# Final_Schematic.net
KiCad netlist of a schematic drawn in Altium Designer
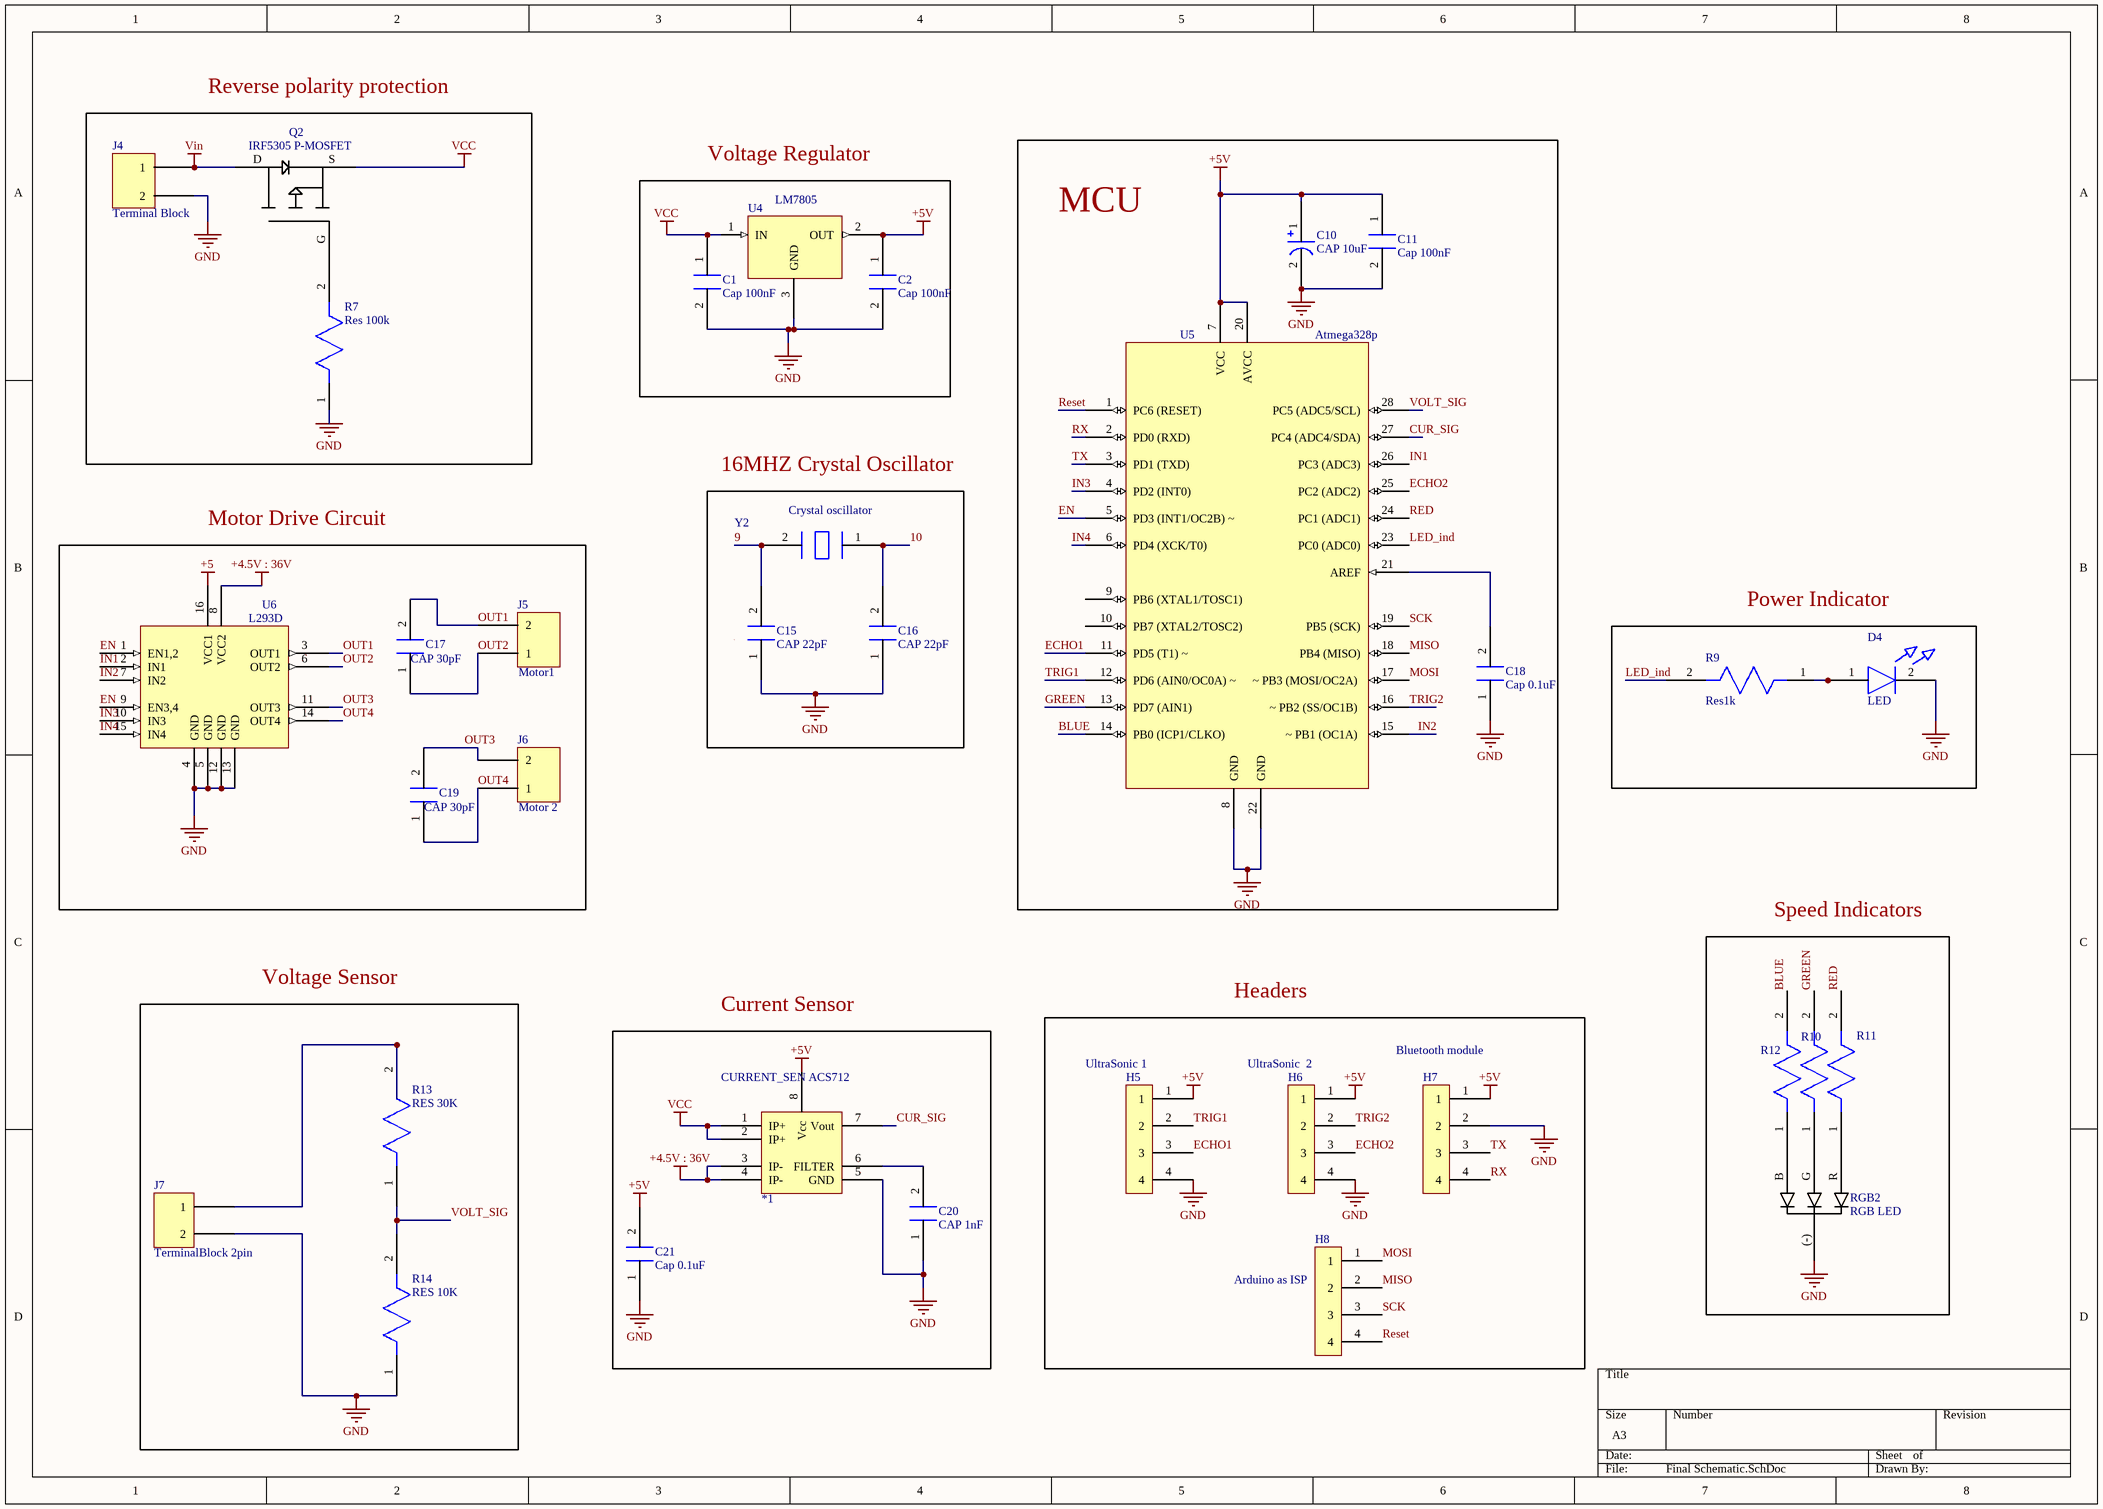
[diagram p0: Final Schematic.SchDoc]

(export (version "E")
  (design (tool "Eeschema 10.0.6"))
  (components
    (comp (ref "*1")
      (value "CURRENT_SEN ACS712")
      (footprint "Cuurent_sens")
      (libsource (lib "Schlib1") (part "CURRENT_MOD ACS712"))
    )
    (comp (ref "C1") (value "Cap 100nF") (libsource (lib "Schematic Library") (part "Cap 100nF")))
    (comp (ref "C2") (value "Cap 100nF") (libsource (lib "Schematic Library") (part "Cap 100nF")))
    (comp (ref "C10")
      (value "CAP 10uF")
      (footprint "Cap 10uF")
      (libsource (lib "Schematic Library") (part "CAP 10uF"))
    )
    (comp (ref "C11") (value "Cap 100nF") (libsource (lib "Schematic Library") (part "Cap 100nF")))
    (comp (ref "C15")
      (value "CAP 22pF")
      (footprint "Cap 22pF")
      (libsource (lib "Schematic Library") (part "CAP 22pF"))
    )
    (comp (ref "C16")
      (value "CAP 22pF")
      (footprint "Cap 22pF")
      (libsource (lib "Schematic Library") (part "CAP 22pF"))
    )
    (comp (ref "C17") (value "CAP 30pF") (libsource (lib "Schlib1") (part "CAP 30pF")))
    (comp (ref "C18") (value "Cap 0.1uF") (libsource (lib "Schematic Library") (part "Cap 0.1uF")))
    (comp (ref "C19") (value "CAP 30pF") (libsource (lib "Schlib1") (part "CAP 30pF")))
    (comp (ref "C20") (value "CAP 1nF") (footprint "CAP 1nF") (libsource (lib "Schlib1") (part "CAP 1nF")))
    (comp (ref "C21")
      (value "Cap 0.1uF")
      (footprint "CAP 0.1uF")
      (libsource (lib "Schlib1") (part "Cap 0.1uF"))
    )
    (comp (ref "D4") (value "LED") (footprint "LED") (libsource (lib "Schematic Library") (part "LED")))
    (comp (ref "H5")
      (value "UltraSonic 1")
      (footprint "Header 4pin")
      (libsource (lib "Schematic Library") (part "Headers 4pin_1"))
    )
    (comp (ref "H6")
      (value "UltraSonic  2")
      (footprint "Header 4pin")
      (libsource (lib "Schematic Library") (part "Headers 4pin_1"))
    )
    (comp (ref "H7")
      (value "Bluetooth module")
      (footprint "Header 4pin")
      (libsource (lib "Schematic Library") (part "Headers 4pin_1"))
    )
    (comp (ref "H8")
      (value "Arduino as ISP")
      (footprint "Header 4pin")
      (libsource (lib "Schematic Library") (part "Headers 4pin_1"))
    )
    (comp (ref "J4")
      (value "Terminal Block")
      (footprint "Terminal Block 2pin")
      (libsource (lib "") (part "Terminal Block_1"))
    )
    (comp (ref "J5")
      (value "Motor1")
      (footprint "Terminal Block 2pin")
      (libsource (lib "Schematic Library") (part "Terminal Block"))
    )
    (comp (ref "J6")
      (value "Motor 2")
      (footprint "Terminal Block 2pin")
      (libsource (lib "Schematic Library") (part "Terminal Block"))
    )
    (comp (ref "J7")
      (value "TerminalBlock 2pin")
      (footprint "Terminal Block 2pin")
      (libsource (lib "Schlib1") (part "TerminalBlock 2pin"))
    )
    (comp (ref "Q2")
      (value "IRF5305 P-MOSFET")
      (footprint "IRF5305")
      (libsource (lib "Schematic Library") (part "IRF5305 P-MOSFET"))
    )
    (comp (ref "R7")
      (value "Res 100k")
      (footprint "Res100K")
      (libsource (lib "Schematic Library") (part "Res 100k"))
    )
    (comp (ref "R9")
      (value "Res1k")
      (footprint "Res 1K")
      (libsource (lib "Schematic Library") (part "Res1k"))
    )
    (comp (ref "R10") (value "Resistor") (libsource (lib "Schematic Library") (part "Resistor")))
    (comp (ref "R11") (value "Resistor") (libsource (lib "Schematic Library") (part "Resistor")))
    (comp (ref "R12") (value "Resistor") (libsource (lib "Schematic Library") (part "Resistor")))
    (comp (ref "R13") (value "RES 30K") (footprint "Res100K") (libsource (lib "Schlib1") (part "RES 100K")))
    (comp (ref "R14") (value "RES 10K") (footprint "Res10K") (libsource (lib "Schlib1") (part "RES 10K")))
    (comp (ref "RGB2")
      (value "RGB LED")
      (footprint "RGB LED")
      (libsource (lib "Schematic Library") (part "RGB LED"))
    )
    (comp (ref "U4")
      (value "LM7805")
      (footprint "LM7805")
      (libsource (lib "Schematic Library") (part "LM7805"))
    )
    (comp (ref "U5")
      (value "Atmega328p")
      (footprint "ATMega 328 P-PU - duplicate")
      (libsource (lib "Schematic Library") (part "Atmega328p"))
    )
    (comp (ref "U6") (value "L293D") (footprint "L293D") (libsource (lib "Schematic Library") (part "L293D")))
    (comp (ref "Y2")
      (value "Crystal oscillator")
      (footprint "Crrystal 16MHZ")
      (libsource (lib "Schematic Library") (part "Crystal oscillator"))
    )
  )
  (nets
    (net (code "1") (name "+4.5V : 36V") (class "Default")
      (node (ref "*1") (pin "3") (pinfunction "IP-_3") (pintype "passive"))
      (node (ref "*1") (pin "4") (pinfunction "IP-_4") (pintype "passive"))
      (node (ref "U6") (pin "8") (pinfunction "VCC2_8") (pintype "power_in"))
    )
    (net (code "2") (name "+5") (class "Default")
      (node (ref "U6") (pin "16") (pinfunction "VCC1_16") (pintype "power_in"))
    )
    (net (code "3") (name "+5V") (class "Default")
      (node (ref "*1") (pin "8") (pinfunction "Vcc_8") (pintype "passive"))
      (node (ref "C10") (pin "1") (pinfunction "1_1") (pintype "passive"))
      (node (ref "C11") (pin "1") (pinfunction "1_1") (pintype "passive"))
      (node (ref "C2") (pin "1") (pinfunction "1_1") (pintype "passive"))
      (node (ref "C21") (pin "2") (pinfunction "2_2") (pintype "passive"))
      (node (ref "H5") (pin "1") (pinfunction "1_1") (pintype "passive"))
      (node (ref "H6") (pin "1") (pinfunction "1_1") (pintype "passive"))
      (node (ref "H7") (pin "1") (pinfunction "1_1") (pintype "passive"))
      (node (ref "U4") (pin "2") (pinfunction "OUT_2") (pintype "output"))
      (node (ref "U5") (pin "20") (pinfunction "AVCC_20") (pintype "passive"))
      (node (ref "U5") (pin "7") (pinfunction "VCC_7") (pintype "passive"))
    )
    (net (code "4") (name "/9") (class "Default")
      (node (ref "C15") (pin "2") (pinfunction "2_2") (pintype "passive"))
      (node (ref "Y2") (pin "2") (pinfunction "2_2") (pintype "passive"))
    )
    (net (code "5") (name "/10") (class "Default")
      (node (ref "C16") (pin "2") (pinfunction "2_2") (pintype "passive"))
      (node (ref "Y2") (pin "1") (pinfunction "1_1") (pintype "passive"))
    )
    (net (code "7") (name "/BLUE") (class "Default")
      (node (ref "R12") (pin "2") (pinfunction "4_2") (pintype "passive"))
      (node (ref "U5") (pin "14") (pinfunction "PB0_(ICP1/CLKO)_14") (pintype "bidirectional"))
    )
    (net (code "8") (name "/CUR_SIG") (class "Default")
      (node (ref "*1") (pin "7") (pinfunction "Vout_7") (pintype "passive"))
      (node (ref "U5") (pin "27") (pinfunction "PC4_(ADC4/SDA)_27") (pintype "bidirectional"))
    )
    (net (code "9") (name "/ECHO1") (class "Default")
      (node (ref "H5") (pin "3") (pinfunction "3_3") (pintype "passive"))
      (node (ref "U5") (pin "11") (pinfunction "PD5_(T1)_~_11") (pintype "bidirectional"))
    )
    (net (code "10") (name "/ECHO2") (class "Default")
      (node (ref "H6") (pin "3") (pinfunction "3_3") (pintype "passive"))
      (node (ref "U5") (pin "25") (pinfunction "PC2_(ADC2)_25") (pintype "bidirectional"))
    )
    (net (code "11") (name "/EN") (class "Default")
      (node (ref "U5") (pin "5") (pinfunction "PD3_(INT1/OC2B)_~_5") (pintype "bidirectional"))
      (node (ref "U6") (pin "1") (pinfunction "EN1,2_1") (pintype "input"))
      (node (ref "U6") (pin "9") (pinfunction "EN3,4_9") (pintype "input"))
    )
    (net (code "12") (name "/GREEN") (class "Default")
      (node (ref "R10") (pin "2") (pinfunction "4_2") (pintype "passive"))
      (node (ref "U5") (pin "13") (pinfunction "PD7_(AIN1)_13") (pintype "bidirectional"))
    )
    (net (code "13") (name "/IN1") (class "Default")
      (node (ref "U5") (pin "26") (pinfunction "PC3_(ADC3)_26") (pintype "bidirectional"))
      (node (ref "U6") (pin "2") (pinfunction "IN1_2") (pintype "input"))
    )
    (net (code "14") (name "/IN2") (class "Default")
      (node (ref "U5") (pin "15") (pinfunction "~_PB1_(OC1A)_15") (pintype "bidirectional"))
      (node (ref "U6") (pin "7") (pinfunction "IN2_7") (pintype "input"))
    )
    (net (code "15") (name "/IN3") (class "Default")
      (node (ref "U5") (pin "4") (pinfunction "PD2_(INT0)_4") (pintype "bidirectional"))
      (node (ref "U6") (pin "10") (pinfunction "IN3_10") (pintype "input"))
    )
    (net (code "16") (name "/IN4") (class "Default")
      (node (ref "U5") (pin "6") (pinfunction "PD4_(XCK/T0)_6") (pintype "bidirectional"))
      (node (ref "U6") (pin "15") (pinfunction "IN4_15") (pintype "input"))
    )
    (net (code "17") (name "/LED_ind") (class "Default")
      (node (ref "R9") (pin "2") (pinfunction "4_2") (pintype "passive"))
      (node (ref "U5") (pin "23") (pinfunction "PC0_(ADC0)_23") (pintype "bidirectional"))
    )
    (net (code "18") (name "/MISO") (class "Default")
      (node (ref "H8") (pin "2") (pinfunction "2_2") (pintype "passive"))
      (node (ref "U5") (pin "18") (pinfunction "PB4_(MISO)_18") (pintype "bidirectional"))
    )
    (net (code "19") (name "/MOSI") (class "Default")
      (node (ref "H8") (pin "1") (pinfunction "1_1") (pintype "passive"))
      (node (ref "U5") (pin "17") (pinfunction "~_PB3_(MOSI/OC2A)_17") (pintype "bidirectional"))
    )
    (net (code "20") (name "/OUT1") (class "Default")
      (node (ref "C17") (pin "2") (pinfunction "2_2") (pintype "passive"))
      (node (ref "J5") (pin "2") (pinfunction "2_2") (pintype "passive"))
      (node (ref "U6") (pin "3") (pinfunction "OUT1_3") (pintype "output"))
    )
    (net (code "21") (name "/OUT2") (class "Default")
      (node (ref "C17") (pin "1") (pinfunction "1_1") (pintype "passive"))
      (node (ref "J5") (pin "1") (pinfunction "1_1") (pintype "passive"))
      (node (ref "U6") (pin "6") (pinfunction "OUT2_6") (pintype "output"))
    )
    (net (code "22") (name "/OUT3") (class "Default")
      (node (ref "C19") (pin "2") (pinfunction "2_2") (pintype "passive"))
      (node (ref "J6") (pin "2") (pinfunction "2_2") (pintype "passive"))
      (node (ref "U6") (pin "11") (pinfunction "OUT3_11") (pintype "output"))
    )
    (net (code "23") (name "/OUT4") (class "Default")
      (node (ref "C19") (pin "1") (pinfunction "1_1") (pintype "passive"))
      (node (ref "J6") (pin "1") (pinfunction "1_1") (pintype "passive"))
      (node (ref "U6") (pin "14") (pinfunction "OUT4_14") (pintype "output"))
    )
    (net (code "24") (name "/RED") (class "Default")
      (node (ref "R11") (pin "2") (pinfunction "4_2") (pintype "passive"))
      (node (ref "U5") (pin "24") (pinfunction "PC1_(ADC1)_24") (pintype "bidirectional"))
    )
    (net (code "25") (name "/RX") (class "Default")
      (node (ref "H7") (pin "4") (pinfunction "4_4") (pintype "passive"))
      (node (ref "U5") (pin "2") (pinfunction "PD0_(RXD)_2") (pintype "bidirectional"))
    )
    (net (code "26") (name "/Reset") (class "Default")
      (node (ref "H8") (pin "4") (pinfunction "4_4") (pintype "passive"))
      (node (ref "U5") (pin "1") (pinfunction "PC6_(RESET)_1") (pintype "bidirectional"))
    )
    (net (code "27") (name "/SCK") (class "Default")
      (node (ref "H8") (pin "3") (pinfunction "3_3") (pintype "passive"))
      (node (ref "U5") (pin "19") (pinfunction "PB5_(SCK)_19") (pintype "bidirectional"))
    )
    (net (code "28") (name "/TRIG1") (class "Default")
      (node (ref "H5") (pin "2") (pinfunction "2_2") (pintype "passive"))
      (node (ref "U5") (pin "12") (pinfunction "PD6_(AIN0/OC0A)_~_12") (pintype "bidirectional"))
    )
    (net (code "29") (name "/TRIG2") (class "Default")
      (node (ref "H6") (pin "2") (pinfunction "2_2") (pintype "passive"))
      (node (ref "U5") (pin "16") (pinfunction "~_PB2_(SS/OC1B)_16") (pintype "bidirectional"))
    )
    (net (code "30") (name "/TX") (class "Default")
      (node (ref "H7") (pin "3") (pinfunction "3_3") (pintype "passive"))
      (node (ref "U5") (pin "3") (pinfunction "PD1_(TXD)_3") (pintype "bidirectional"))
    )
    (net (code "31") (name "/VOLT_SIG") (class "Default")
      (node (ref "R13") (pin "1") (pinfunction "3_1") (pintype "passive"))
      (node (ref "R14") (pin "2") (pinfunction "4_2") (pintype "passive"))
      (node (ref "U5") (pin "28") (pinfunction "PC5_(ADC5/SCL)_28") (pintype "bidirectional"))
    )
    (net (code "32") (name "GND") (class "Default")
      (node (ref "*1") (pin "5") (pinfunction "GND_5") (pintype "passive"))
      (node (ref "C1") (pin "2") (pinfunction "2_2") (pintype "passive"))
      (node (ref "C10") (pin "2") (pinfunction "2_2") (pintype "passive"))
      (node (ref "C11") (pin "2") (pinfunction "2_2") (pintype "passive"))
      (node (ref "C15") (pin "1") (pinfunction "1_1") (pintype "passive"))
      (node (ref "C16") (pin "1") (pinfunction "1_1") (pintype "passive"))
      (node (ref "C18") (pin "1") (pinfunction "1_1") (pintype "passive"))
      (node (ref "C2") (pin "2") (pinfunction "2_2") (pintype "passive"))
      (node (ref "C20") (pin "1") (pinfunction "1_1") (pintype "passive"))
      (node (ref "C21") (pin "1") (pinfunction "1_1") (pintype "passive"))
      (node (ref "D4") (pin "2") (pinfunction "6_2") (pintype "passive"))
      (node (ref "H5") (pin "4") (pinfunction "4_4") (pintype "passive"))
      (node (ref "H6") (pin "4") (pinfunction "4_4") (pintype "passive"))
      (node (ref "H7") (pin "2") (pinfunction "2_2") (pintype "passive"))
      (node (ref "J4") (pin "2") (pinfunction "2_2") (pintype "passive"))
      (node (ref "J7") (pin "2") (pinfunction "2_2") (pintype "passive"))
      (node (ref "R14") (pin "1") (pinfunction "3_1") (pintype "passive"))
      (node (ref "R7") (pin "1") (pinfunction "3_1") (pintype "passive"))
      (node (ref "RGB2") (pin "(-)") (pinfunction "1_(-)") (pintype "passive"))
      (node (ref "U4") (pin "3") (pinfunction "GND_3") (pintype "power_in"))
      (node (ref "U5") (pin "22") (pinfunction "GND_22") (pintype "passive"))
      (node (ref "U5") (pin "8") (pinfunction "GND_8") (pintype "passive"))
      (node (ref "U6") (pin "12") (pinfunction "GND_12") (pintype "power_in"))
      (node (ref "U6") (pin "13") (pinfunction "GND_13") (pintype "power_in"))
      (node (ref "U6") (pin "4") (pinfunction "GND_4") (pintype "power_in"))
      (node (ref "U6") (pin "5") (pinfunction "GND_5") (pintype "power_in"))
    )
    (net (code "33") (name "Net-(*1-FILTER)") (class "Default")
      (node (ref "*1") (pin "6") (pinfunction "FILTER_6") (pintype "passive"))
      (node (ref "C20") (pin "2") (pinfunction "2_2") (pintype "passive"))
    )
    (net (code "34") (name "Net-(D4-7)") (class "Default")
      (node (ref "D4") (pin "1") (pinfunction "7_1") (pintype "passive"))
      (node (ref "R9") (pin "1") (pinfunction "3_1") (pintype "passive"))
    )
    (net (code "35") (name "Net-(Q2-1)") (class "Default")
      (node (ref "Q2") (pin "G") (pinfunction "1_G") (pintype "passive"))
      (node (ref "R7") (pin "2") (pinfunction "4_2") (pintype "passive"))
    )
    (net (code "36") (name "Net-(R10-3)") (class "Default")
      (node (ref "R10") (pin "1") (pinfunction "3_1") (pintype "passive"))
      (node (ref "RGB2") (pin "G") (pinfunction "3_G") (pintype "passive"))
    )
    (net (code "37") (name "Net-(R11-3)") (class "Default")
      (node (ref "R11") (pin "1") (pinfunction "3_1") (pintype "passive"))
      (node (ref "RGB2") (pin "R") (pinfunction "2_R") (pintype "passive"))
    )
    (net (code "38") (name "Net-(R12-3)") (class "Default")
      (node (ref "R12") (pin "1") (pinfunction "3_1") (pintype "passive"))
      (node (ref "RGB2") (pin "B") (pinfunction "4_B") (pintype "passive"))
    )
    (net (code "39") (name "Net-(R13-4)") (class "Default")
      (node (ref "J7") (pin "1") (pinfunction "1_1") (pintype "passive"))
      (node (ref "R13") (pin "2") (pinfunction "4_2") (pintype "passive"))
    )
    (net (code "40") (name "Net-(U5-AREF)") (class "Default")
      (node (ref "C18") (pin "2") (pinfunction "2_2") (pintype "passive"))
      (node (ref "U5") (pin "21") (pinfunction "AREF_21") (pintype "input"))
    )
    (net (code "41") (name "VCC") (class "Default")
      (node (ref "*1") (pin "1") (pinfunction "IP+_1") (pintype "passive"))
      (node (ref "*1") (pin "2") (pinfunction "IP+_2") (pintype "passive"))
      (node (ref "C1") (pin "1") (pinfunction "1_1") (pintype "passive"))
      (node (ref "Q2") (pin "S") (pinfunction "2_S") (pintype "passive"))
      (node (ref "U4") (pin "1") (pinfunction "IN_1") (pintype "input"))
    )
    (net (code "42") (name "Vin") (class "Default")
      (node (ref "J4") (pin "1") (pinfunction "1_1") (pintype "passive"))
      (node (ref "Q2") (pin "D") (pinfunction "3_D") (pintype "passive"))
    )
    (net (code "43") (name "unconnected-(U5-PB6_(XTAL1{slash}TOSC1)-Pad9)") (class "Default")
      (node (ref "U5") (pin "9") (pinfunction "PB6_(XTAL1/TOSC1)_9") (pintype "bidirectional"))
    )
    (net (code "44") (name "unconnected-(U5-PB7_(XTAL2{slash}TOSC2)-Pad10)") (class "Default")
      (node (ref "U5") (pin "10") (pinfunction "PB7_(XTAL2/TOSC2)_10") (pintype "bidirectional"))
    )
  )
)
